# output_charlieplex_12x11.net
KiCad netlist of a schematic drawn in EasyEDA
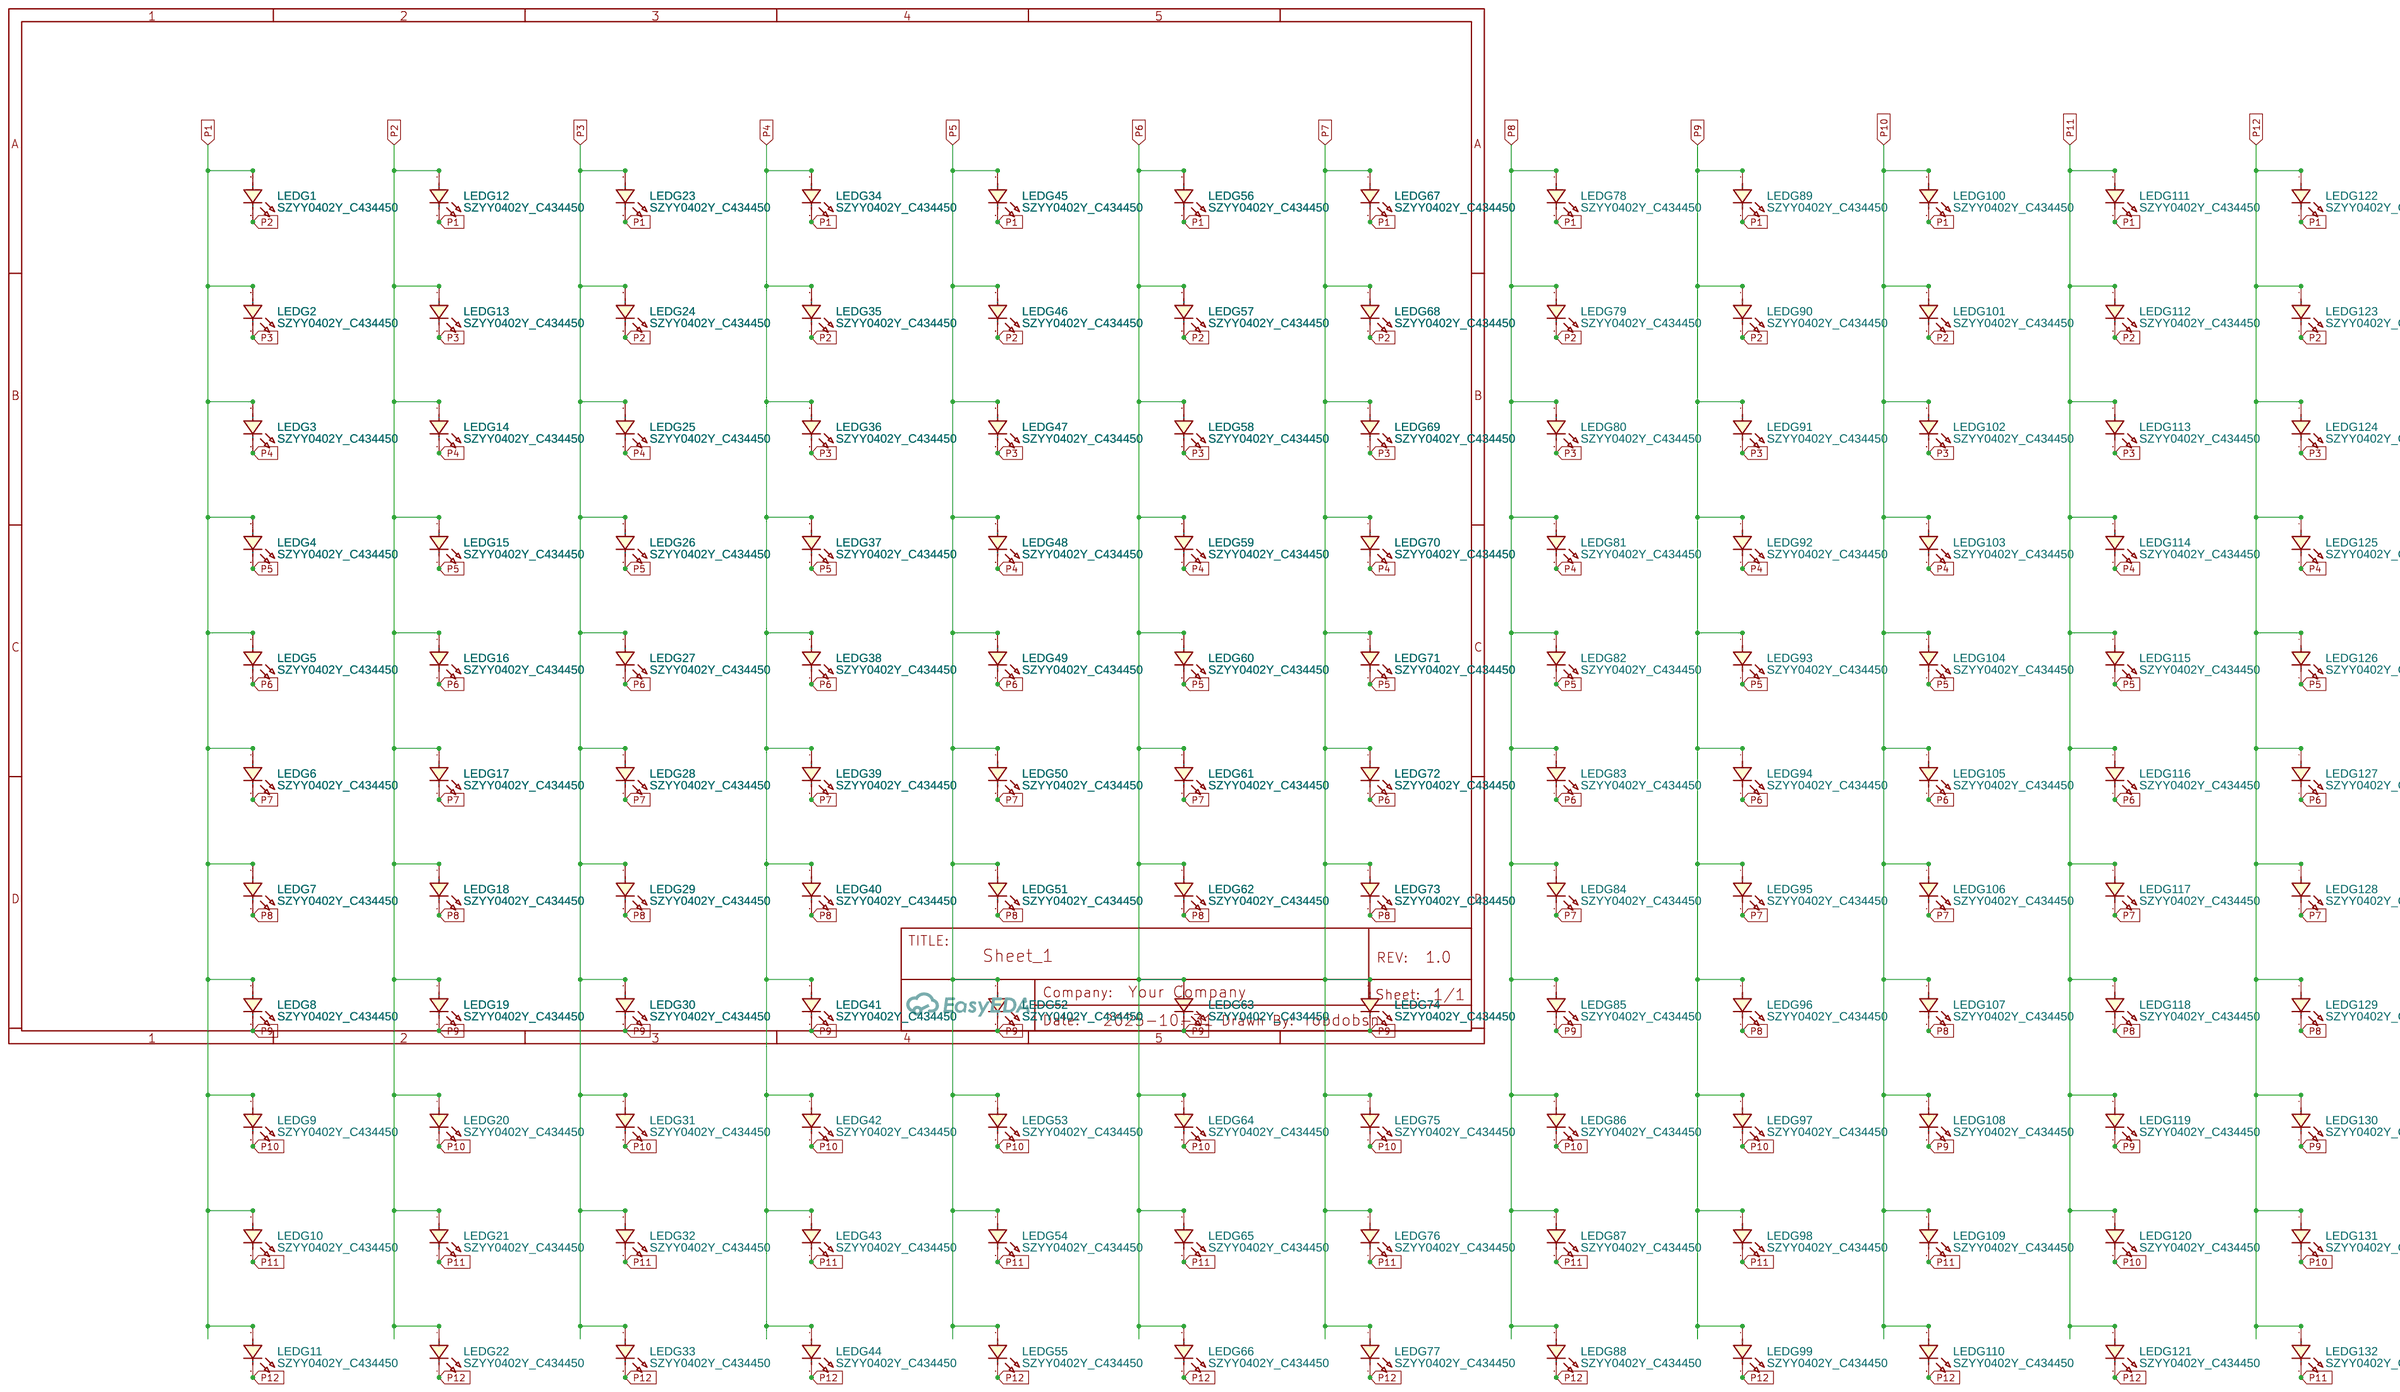
[diagram p0: schematic sheet]

(export (version "E")
  (design (tool "Eeschema 10.0.6"))
  (components
    (comp (ref "LEDG1")
      (value "SZYY0402Y_C434450")
      (fields (field (name "Manufacturer Part") "SZYY0402Y") (field (name "Manufacturer") "yongyu(永裕光电)"))
      (libsource (lib "") (part "SZYY0402Y_C434450"))
    )
    (comp (ref "LEDG2")
      (value "SZYY0402Y_C434450")
      (fields (field (name "Manufacturer Part") "SZYY0402Y") (field (name "Manufacturer") "yongyu(永裕光电)"))
      (libsource (lib "") (part "SZYY0402Y_C434450"))
    )
    (comp (ref "LEDG3")
      (value "SZYY0402Y_C434450")
      (fields (field (name "Manufacturer Part") "SZYY0402Y") (field (name "Manufacturer") "yongyu(永裕光电)"))
      (libsource (lib "") (part "SZYY0402Y_C434450"))
    )
    (comp (ref "LEDG4")
      (value "SZYY0402Y_C434450")
      (fields (field (name "Manufacturer Part") "SZYY0402Y") (field (name "Manufacturer") "yongyu(永裕光电)"))
      (libsource (lib "") (part "SZYY0402Y_C434450"))
    )
    (comp (ref "LEDG5")
      (value "SZYY0402Y_C434450")
      (fields (field (name "Manufacturer Part") "SZYY0402Y") (field (name "Manufacturer") "yongyu(永裕光电)"))
      (libsource (lib "") (part "SZYY0402Y_C434450"))
    )
    (comp (ref "LEDG6")
      (value "SZYY0402Y_C434450")
      (fields (field (name "Manufacturer Part") "SZYY0402Y") (field (name "Manufacturer") "yongyu(永裕光电)"))
      (libsource (lib "") (part "SZYY0402Y_C434450"))
    )
    (comp (ref "LEDG7")
      (value "SZYY0402Y_C434450")
      (fields (field (name "Manufacturer Part") "SZYY0402Y") (field (name "Manufacturer") "yongyu(永裕光电)"))
      (libsource (lib "") (part "SZYY0402Y_C434450"))
    )
    (comp (ref "LEDG8")
      (value "SZYY0402Y_C434450")
      (fields (field (name "Manufacturer Part") "SZYY0402Y") (field (name "Manufacturer") "yongyu(永裕光电)"))
      (libsource (lib "") (part "SZYY0402Y_C434450"))
    )
    (comp (ref "LEDG9")
      (value "SZYY0402Y_C434450")
      (fields (field (name "Manufacturer Part") "SZYY0402Y") (field (name "Manufacturer") "yongyu(永裕光电)"))
      (libsource (lib "") (part "SZYY0402Y_C434450"))
    )
    (comp (ref "LEDG10")
      (value "SZYY0402Y_C434450")
      (fields (field (name "Manufacturer Part") "SZYY0402Y") (field (name "Manufacturer") "yongyu(永裕光电)"))
      (libsource (lib "") (part "SZYY0402Y_C434450"))
    )
    (comp (ref "LEDG11")
      (value "SZYY0402Y_C434450")
      (fields (field (name "Manufacturer Part") "SZYY0402Y") (field (name "Manufacturer") "yongyu(永裕光电)"))
      (libsource (lib "") (part "SZYY0402Y_C434450"))
    )
    (comp (ref "LEDG12")
      (value "SZYY0402Y_C434450")
      (fields (field (name "Manufacturer Part") "SZYY0402Y") (field (name "Manufacturer") "yongyu(永裕光电)"))
      (libsource (lib "") (part "SZYY0402Y_C434450"))
    )
    (comp (ref "LEDG13")
      (value "SZYY0402Y_C434450")
      (fields (field (name "Manufacturer Part") "SZYY0402Y") (field (name "Manufacturer") "yongyu(永裕光电)"))
      (libsource (lib "") (part "SZYY0402Y_C434450"))
    )
    (comp (ref "LEDG14")
      (value "SZYY0402Y_C434450")
      (fields (field (name "Manufacturer Part") "SZYY0402Y") (field (name "Manufacturer") "yongyu(永裕光电)"))
      (libsource (lib "") (part "SZYY0402Y_C434450"))
    )
    (comp (ref "LEDG15")
      (value "SZYY0402Y_C434450")
      (fields (field (name "Manufacturer Part") "SZYY0402Y") (field (name "Manufacturer") "yongyu(永裕光电)"))
      (libsource (lib "") (part "SZYY0402Y_C434450"))
    )
    (comp (ref "LEDG16")
      (value "SZYY0402Y_C434450")
      (fields (field (name "Manufacturer Part") "SZYY0402Y") (field (name "Manufacturer") "yongyu(永裕光电)"))
      (libsource (lib "") (part "SZYY0402Y_C434450"))
    )
    (comp (ref "LEDG17")
      (value "SZYY0402Y_C434450")
      (fields (field (name "Manufacturer Part") "SZYY0402Y") (field (name "Manufacturer") "yongyu(永裕光电)"))
      (libsource (lib "") (part "SZYY0402Y_C434450"))
    )
    (comp (ref "LEDG18")
      (value "SZYY0402Y_C434450")
      (fields (field (name "Manufacturer Part") "SZYY0402Y") (field (name "Manufacturer") "yongyu(永裕光电)"))
      (libsource (lib "") (part "SZYY0402Y_C434450"))
    )
    (comp (ref "LEDG19")
      (value "SZYY0402Y_C434450")
      (fields (field (name "Manufacturer Part") "SZYY0402Y") (field (name "Manufacturer") "yongyu(永裕光电)"))
      (libsource (lib "") (part "SZYY0402Y_C434450"))
    )
    (comp (ref "LEDG20")
      (value "SZYY0402Y_C434450")
      (fields (field (name "Manufacturer Part") "SZYY0402Y") (field (name "Manufacturer") "yongyu(永裕光电)"))
      (libsource (lib "") (part "SZYY0402Y_C434450"))
    )
    (comp (ref "LEDG21")
      (value "SZYY0402Y_C434450")
      (fields (field (name "Manufacturer Part") "SZYY0402Y") (field (name "Manufacturer") "yongyu(永裕光电)"))
      (libsource (lib "") (part "SZYY0402Y_C434450"))
    )
    (comp (ref "LEDG22")
      (value "SZYY0402Y_C434450")
      (fields (field (name "Manufacturer Part") "SZYY0402Y") (field (name "Manufacturer") "yongyu(永裕光电)"))
      (libsource (lib "") (part "SZYY0402Y_C434450"))
    )
    (comp (ref "LEDG23")
      (value "SZYY0402Y_C434450")
      (fields (field (name "Manufacturer Part") "SZYY0402Y") (field (name "Manufacturer") "yongyu(永裕光电)"))
      (libsource (lib "") (part "SZYY0402Y_C434450"))
    )
    (comp (ref "LEDG24")
      (value "SZYY0402Y_C434450")
      (fields (field (name "Manufacturer Part") "SZYY0402Y") (field (name "Manufacturer") "yongyu(永裕光电)"))
      (libsource (lib "") (part "SZYY0402Y_C434450"))
    )
    (comp (ref "LEDG25")
      (value "SZYY0402Y_C434450")
      (fields (field (name "Manufacturer Part") "SZYY0402Y") (field (name "Manufacturer") "yongyu(永裕光电)"))
      (libsource (lib "") (part "SZYY0402Y_C434450"))
    )
    (comp (ref "LEDG26")
      (value "SZYY0402Y_C434450")
      (fields (field (name "Manufacturer Part") "SZYY0402Y") (field (name "Manufacturer") "yongyu(永裕光电)"))
      (libsource (lib "") (part "SZYY0402Y_C434450"))
    )
    (comp (ref "LEDG27")
      (value "SZYY0402Y_C434450")
      (fields (field (name "Manufacturer Part") "SZYY0402Y") (field (name "Manufacturer") "yongyu(永裕光电)"))
      (libsource (lib "") (part "SZYY0402Y_C434450"))
    )
    (comp (ref "LEDG28")
      (value "SZYY0402Y_C434450")
      (fields (field (name "Manufacturer Part") "SZYY0402Y") (field (name "Manufacturer") "yongyu(永裕光电)"))
      (libsource (lib "") (part "SZYY0402Y_C434450"))
    )
    (comp (ref "LEDG29")
      (value "SZYY0402Y_C434450")
      (fields (field (name "Manufacturer Part") "SZYY0402Y") (field (name "Manufacturer") "yongyu(永裕光电)"))
      (libsource (lib "") (part "SZYY0402Y_C434450"))
    )
    (comp (ref "LEDG30")
      (value "SZYY0402Y_C434450")
      (fields (field (name "Manufacturer Part") "SZYY0402Y") (field (name "Manufacturer") "yongyu(永裕光电)"))
      (libsource (lib "") (part "SZYY0402Y_C434450"))
    )
    (comp (ref "LEDG31")
      (value "SZYY0402Y_C434450")
      (fields (field (name "Manufacturer Part") "SZYY0402Y") (field (name "Manufacturer") "yongyu(永裕光电)"))
      (libsource (lib "") (part "SZYY0402Y_C434450"))
    )
    (comp (ref "LEDG32")
      (value "SZYY0402Y_C434450")
      (fields (field (name "Manufacturer Part") "SZYY0402Y") (field (name "Manufacturer") "yongyu(永裕光电)"))
      (libsource (lib "") (part "SZYY0402Y_C434450"))
    )
    (comp (ref "LEDG33")
      (value "SZYY0402Y_C434450")
      (fields (field (name "Manufacturer Part") "SZYY0402Y") (field (name "Manufacturer") "yongyu(永裕光电)"))
      (libsource (lib "") (part "SZYY0402Y_C434450"))
    )
    (comp (ref "LEDG34")
      (value "SZYY0402Y_C434450")
      (fields (field (name "Manufacturer Part") "SZYY0402Y") (field (name "Manufacturer") "yongyu(永裕光电)"))
      (libsource (lib "") (part "SZYY0402Y_C434450"))
    )
    (comp (ref "LEDG35")
      (value "SZYY0402Y_C434450")
      (fields (field (name "Manufacturer Part") "SZYY0402Y") (field (name "Manufacturer") "yongyu(永裕光电)"))
      (libsource (lib "") (part "SZYY0402Y_C434450"))
    )
    (comp (ref "LEDG36")
      (value "SZYY0402Y_C434450")
      (fields (field (name "Manufacturer Part") "SZYY0402Y") (field (name "Manufacturer") "yongyu(永裕光电)"))
      (libsource (lib "") (part "SZYY0402Y_C434450"))
    )
    (comp (ref "LEDG37")
      (value "SZYY0402Y_C434450")
      (fields (field (name "Manufacturer Part") "SZYY0402Y") (field (name "Manufacturer") "yongyu(永裕光电)"))
      (libsource (lib "") (part "SZYY0402Y_C434450"))
    )
    (comp (ref "LEDG38")
      (value "SZYY0402Y_C434450")
      (fields (field (name "Manufacturer Part") "SZYY0402Y") (field (name "Manufacturer") "yongyu(永裕光电)"))
      (libsource (lib "") (part "SZYY0402Y_C434450"))
    )
    (comp (ref "LEDG39")
      (value "SZYY0402Y_C434450")
      (fields (field (name "Manufacturer Part") "SZYY0402Y") (field (name "Manufacturer") "yongyu(永裕光电)"))
      (libsource (lib "") (part "SZYY0402Y_C434450"))
    )
    (comp (ref "LEDG40")
      (value "SZYY0402Y_C434450")
      (fields (field (name "Manufacturer Part") "SZYY0402Y") (field (name "Manufacturer") "yongyu(永裕光电)"))
      (libsource (lib "") (part "SZYY0402Y_C434450"))
    )
    (comp (ref "LEDG41")
      (value "SZYY0402Y_C434450")
      (fields (field (name "Manufacturer Part") "SZYY0402Y") (field (name "Manufacturer") "yongyu(永裕光电)"))
      (libsource (lib "") (part "SZYY0402Y_C434450"))
    )
    (comp (ref "LEDG42")
      (value "SZYY0402Y_C434450")
      (fields (field (name "Manufacturer Part") "SZYY0402Y") (field (name "Manufacturer") "yongyu(永裕光电)"))
      (libsource (lib "") (part "SZYY0402Y_C434450"))
    )
    (comp (ref "LEDG43")
      (value "SZYY0402Y_C434450")
      (fields (field (name "Manufacturer Part") "SZYY0402Y") (field (name "Manufacturer") "yongyu(永裕光电)"))
      (libsource (lib "") (part "SZYY0402Y_C434450"))
    )
    (comp (ref "LEDG44")
      (value "SZYY0402Y_C434450")
      (fields (field (name "Manufacturer Part") "SZYY0402Y") (field (name "Manufacturer") "yongyu(永裕光电)"))
      (libsource (lib "") (part "SZYY0402Y_C434450"))
    )
    (comp (ref "LEDG45")
      (value "SZYY0402Y_C434450")
      (fields (field (name "Manufacturer Part") "SZYY0402Y") (field (name "Manufacturer") "yongyu(永裕光电)"))
      (libsource (lib "") (part "SZYY0402Y_C434450"))
    )
    (comp (ref "LEDG46")
      (value "SZYY0402Y_C434450")
      (fields (field (name "Manufacturer Part") "SZYY0402Y") (field (name "Manufacturer") "yongyu(永裕光电)"))
      (libsource (lib "") (part "SZYY0402Y_C434450"))
    )
    (comp (ref "LEDG47")
      (value "SZYY0402Y_C434450")
      (fields (field (name "Manufacturer Part") "SZYY0402Y") (field (name "Manufacturer") "yongyu(永裕光电)"))
      (libsource (lib "") (part "SZYY0402Y_C434450"))
    )
    (comp (ref "LEDG48")
      (value "SZYY0402Y_C434450")
      (fields (field (name "Manufacturer Part") "SZYY0402Y") (field (name "Manufacturer") "yongyu(永裕光电)"))
      (libsource (lib "") (part "SZYY0402Y_C434450"))
    )
    (comp (ref "LEDG49")
      (value "SZYY0402Y_C434450")
      (fields (field (name "Manufacturer Part") "SZYY0402Y") (field (name "Manufacturer") "yongyu(永裕光电)"))
      (libsource (lib "") (part "SZYY0402Y_C434450"))
    )
    (comp (ref "LEDG50")
      (value "SZYY0402Y_C434450")
      (fields (field (name "Manufacturer Part") "SZYY0402Y") (field (name "Manufacturer") "yongyu(永裕光电)"))
      (libsource (lib "") (part "SZYY0402Y_C434450"))
    )
    (comp (ref "LEDG51")
      (value "SZYY0402Y_C434450")
      (fields (field (name "Manufacturer Part") "SZYY0402Y") (field (name "Manufacturer") "yongyu(永裕光电)"))
      (libsource (lib "") (part "SZYY0402Y_C434450"))
    )
    (comp (ref "LEDG52")
      (value "SZYY0402Y_C434450")
      (fields (field (name "Manufacturer Part") "SZYY0402Y") (field (name "Manufacturer") "yongyu(永裕光电)"))
      (libsource (lib "") (part "SZYY0402Y_C434450"))
    )
    (comp (ref "LEDG53")
      (value "SZYY0402Y_C434450")
      (fields (field (name "Manufacturer Part") "SZYY0402Y") (field (name "Manufacturer") "yongyu(永裕光电)"))
      (libsource (lib "") (part "SZYY0402Y_C434450"))
    )
    (comp (ref "LEDG54")
      (value "SZYY0402Y_C434450")
      (fields (field (name "Manufacturer Part") "SZYY0402Y") (field (name "Manufacturer") "yongyu(永裕光电)"))
      (libsource (lib "") (part "SZYY0402Y_C434450"))
    )
    (comp (ref "LEDG55")
      (value "SZYY0402Y_C434450")
      (fields (field (name "Manufacturer Part") "SZYY0402Y") (field (name "Manufacturer") "yongyu(永裕光电)"))
      (libsource (lib "") (part "SZYY0402Y_C434450"))
    )
    (comp (ref "LEDG56")
      (value "SZYY0402Y_C434450")
      (fields (field (name "Manufacturer Part") "SZYY0402Y") (field (name "Manufacturer") "yongyu(永裕光电)"))
      (libsource (lib "") (part "SZYY0402Y_C434450"))
    )
    (comp (ref "LEDG57")
      (value "SZYY0402Y_C434450")
      (fields (field (name "Manufacturer Part") "SZYY0402Y") (field (name "Manufacturer") "yongyu(永裕光电)"))
      (libsource (lib "") (part "SZYY0402Y_C434450"))
    )
    (comp (ref "LEDG58")
      (value "SZYY0402Y_C434450")
      (fields (field (name "Manufacturer Part") "SZYY0402Y") (field (name "Manufacturer") "yongyu(永裕光电)"))
      (libsource (lib "") (part "SZYY0402Y_C434450"))
    )
    (comp (ref "LEDG59")
      (value "SZYY0402Y_C434450")
      (fields (field (name "Manufacturer Part") "SZYY0402Y") (field (name "Manufacturer") "yongyu(永裕光电)"))
      (libsource (lib "") (part "SZYY0402Y_C434450"))
    )
    (comp (ref "LEDG60")
      (value "SZYY0402Y_C434450")
      (fields (field (name "Manufacturer Part") "SZYY0402Y") (field (name "Manufacturer") "yongyu(永裕光电)"))
      (libsource (lib "") (part "SZYY0402Y_C434450"))
    )
    (comp (ref "LEDG61")
      (value "SZYY0402Y_C434450")
      (fields (field (name "Manufacturer Part") "SZYY0402Y") (field (name "Manufacturer") "yongyu(永裕光电)"))
      (libsource (lib "") (part "SZYY0402Y_C434450"))
    )
    (comp (ref "LEDG62")
      (value "SZYY0402Y_C434450")
      (fields (field (name "Manufacturer Part") "SZYY0402Y") (field (name "Manufacturer") "yongyu(永裕光电)"))
      (libsource (lib "") (part "SZYY0402Y_C434450"))
    )
    (comp (ref "LEDG63")
      (value "SZYY0402Y_C434450")
      (fields (field (name "Manufacturer Part") "SZYY0402Y") (field (name "Manufacturer") "yongyu(永裕光电)"))
      (libsource (lib "") (part "SZYY0402Y_C434450"))
    )
    (comp (ref "LEDG64")
      (value "SZYY0402Y_C434450")
      (fields (field (name "Manufacturer Part") "SZYY0402Y") (field (name "Manufacturer") "yongyu(永裕光电)"))
      (libsource (lib "") (part "SZYY0402Y_C434450"))
    )
    (comp (ref "LEDG65")
      (value "SZYY0402Y_C434450")
      (fields (field (name "Manufacturer Part") "SZYY0402Y") (field (name "Manufacturer") "yongyu(永裕光电)"))
      (libsource (lib "") (part "SZYY0402Y_C434450"))
    )
    (comp (ref "LEDG66")
      (value "SZYY0402Y_C434450")
      (fields (field (name "Manufacturer Part") "SZYY0402Y") (field (name "Manufacturer") "yongyu(永裕光电)"))
      (libsource (lib "") (part "SZYY0402Y_C434450"))
    )
    (comp (ref "LEDG67")
      (value "SZYY0402Y_C434450")
      (fields (field (name "Manufacturer Part") "SZYY0402Y") (field (name "Manufacturer") "yongyu(永裕光电)"))
      (libsource (lib "") (part "SZYY0402Y_C434450"))
    )
    (comp (ref "LEDG68")
      (value "SZYY0402Y_C434450")
      (fields (field (name "Manufacturer Part") "SZYY0402Y") (field (name "Manufacturer") "yongyu(永裕光电)"))
      (libsource (lib "") (part "SZYY0402Y_C434450"))
    )
    (comp (ref "LEDG69")
      (value "SZYY0402Y_C434450")
      (fields (field (name "Manufacturer Part") "SZYY0402Y") (field (name "Manufacturer") "yongyu(永裕光电)"))
      (libsource (lib "") (part "SZYY0402Y_C434450"))
    )
    (comp (ref "LEDG70")
      (value "SZYY0402Y_C434450")
      (fields (field (name "Manufacturer Part") "SZYY0402Y") (field (name "Manufacturer") "yongyu(永裕光电)"))
      (libsource (lib "") (part "SZYY0402Y_C434450"))
    )
    (comp (ref "LEDG71")
      (value "SZYY0402Y_C434450")
      (fields (field (name "Manufacturer Part") "SZYY0402Y") (field (name "Manufacturer") "yongyu(永裕光电)"))
      (libsource (lib "") (part "SZYY0402Y_C434450"))
    )
    (comp (ref "LEDG72")
      (value "SZYY0402Y_C434450")
      (fields (field (name "Manufacturer Part") "SZYY0402Y") (field (name "Manufacturer") "yongyu(永裕光电)"))
      (libsource (lib "") (part "SZYY0402Y_C434450"))
    )
    (comp (ref "LEDG73")
      (value "SZYY0402Y_C434450")
      (fields (field (name "Manufacturer Part") "SZYY0402Y") (field (name "Manufacturer") "yongyu(永裕光电)"))
      (libsource (lib "") (part "SZYY0402Y_C434450"))
    )
    (comp (ref "LEDG74")
      (value "SZYY0402Y_C434450")
      (fields (field (name "Manufacturer Part") "SZYY0402Y") (field (name "Manufacturer") "yongyu(永裕光电)"))
      (libsource (lib "") (part "SZYY0402Y_C434450"))
    )
    (comp (ref "LEDG75")
      (value "SZYY0402Y_C434450")
      (fields (field (name "Manufacturer Part") "SZYY0402Y") (field (name "Manufacturer") "yongyu(永裕光电)"))
      (libsource (lib "") (part "SZYY0402Y_C434450"))
    )
    (comp (ref "LEDG76")
      (value "SZYY0402Y_C434450")
      (fields (field (name "Manufacturer Part") "SZYY0402Y") (field (name "Manufacturer") "yongyu(永裕光电)"))
      (libsource (lib "") (part "SZYY0402Y_C434450"))
    )
    (comp (ref "LEDG77")
      (value "SZYY0402Y_C434450")
      (fields (field (name "Manufacturer Part") "SZYY0402Y") (field (name "Manufacturer") "yongyu(永裕光电)"))
      (libsource (lib "") (part "SZYY0402Y_C434450"))
    )
    (comp (ref "LEDG78")
      (value "SZYY0402Y_C434450")
      (fields (field (name "Manufacturer Part") "SZYY0402Y") (field (name "Manufacturer") "yongyu(永裕光电)"))
      (libsource (lib "") (part "SZYY0402Y_C434450"))
    )
    (comp (ref "LEDG79")
      (value "SZYY0402Y_C434450")
      (fields (field (name "Manufacturer Part") "SZYY0402Y") (field (name "Manufacturer") "yongyu(永裕光电)"))
      (libsource (lib "") (part "SZYY0402Y_C434450"))
    )
    (comp (ref "LEDG80")
      (value "SZYY0402Y_C434450")
      (fields (field (name "Manufacturer Part") "SZYY0402Y") (field (name "Manufacturer") "yongyu(永裕光电)"))
      (libsource (lib "") (part "SZYY0402Y_C434450"))
    )
    (comp (ref "LEDG81")
      (value "SZYY0402Y_C434450")
      (fields (field (name "Manufacturer Part") "SZYY0402Y") (field (name "Manufacturer") "yongyu(永裕光电)"))
      (libsource (lib "") (part "SZYY0402Y_C434450"))
    )
    (comp (ref "LEDG82")
      (value "SZYY0402Y_C434450")
      (fields (field (name "Manufacturer Part") "SZYY0402Y") (field (name "Manufacturer") "yongyu(永裕光电)"))
      (libsource (lib "") (part "SZYY0402Y_C434450"))
    )
    (comp (ref "LEDG83")
      (value "SZYY0402Y_C434450")
      (fields (field (name "Manufacturer Part") "SZYY0402Y") (field (name "Manufacturer") "yongyu(永裕光电)"))
      (libsource (lib "") (part "SZYY0402Y_C434450"))
    )
    (comp (ref "LEDG84")
      (value "SZYY0402Y_C434450")
      (fields (field (name "Manufacturer Part") "SZYY0402Y") (field (name "Manufacturer") "yongyu(永裕光电)"))
      (libsource (lib "") (part "SZYY0402Y_C434450"))
    )
    (comp (ref "LEDG85")
      (value "SZYY0402Y_C434450")
      (fields (field (name "Manufacturer Part") "SZYY0402Y") (field (name "Manufacturer") "yongyu(永裕光电)"))
      (libsource (lib "") (part "SZYY0402Y_C434450"))
    )
    (comp (ref "LEDG86")
      (value "SZYY0402Y_C434450")
      (fields (field (name "Manufacturer Part") "SZYY0402Y") (field (name "Manufacturer") "yongyu(永裕光电)"))
      (libsource (lib "") (part "SZYY0402Y_C434450"))
    )
    (comp (ref "LEDG87")
      (value "SZYY0402Y_C434450")
      (fields (field (name "Manufacturer Part") "SZYY0402Y") (field (name "Manufacturer") "yongyu(永裕光电)"))
      (libsource (lib "") (part "SZYY0402Y_C434450"))
    )
    (comp (ref "LEDG88")
      (value "SZYY0402Y_C434450")
      (fields (field (name "Manufacturer Part") "SZYY0402Y") (field (name "Manufacturer") "yongyu(永裕光电)"))
      (libsource (lib "") (part "SZYY0402Y_C434450"))
    )
    (comp (ref "LEDG89")
      (value "SZYY0402Y_C434450")
      (fields (field (name "Manufacturer Part") "SZYY0402Y") (field (name "Manufacturer") "yongyu(永裕光电)"))
      (libsource (lib "") (part "SZYY0402Y_C434450"))
    )
    (comp (ref "LEDG90")
      (value "SZYY0402Y_C434450")
      (fields (field (name "Manufacturer Part") "SZYY0402Y") (field (name "Manufacturer") "yongyu(永裕光电)"))
      (libsource (lib "") (part "SZYY0402Y_C434450"))
    )
    (comp (ref "LEDG91")
      (value "SZYY0402Y_C434450")
      (fields (field (name "Manufacturer Part") "SZYY0402Y") (field (name "Manufacturer") "yongyu(永裕光电)"))
      (libsource (lib "") (part "SZYY0402Y_C434450"))
    )
    (comp (ref "LEDG92")
      (value "SZYY0402Y_C434450")
      (fields (field (name "Manufacturer Part") "SZYY0402Y") (field (name "Manufacturer") "yongyu(永裕光电)"))
      (libsource (lib "") (part "SZYY0402Y_C434450"))
    )
    (comp (ref "LEDG93")
      (value "SZYY0402Y_C434450")
      (fields (field (name "Manufacturer Part") "SZYY0402Y") (field (name "Manufacturer") "yongyu(永裕光电)"))
      (libsource (lib "") (part "SZYY0402Y_C434450"))
    )
    (comp (ref "LEDG94")
      (value "SZYY0402Y_C434450")
      (fields (field (name "Manufacturer Part") "SZYY0402Y") (field (name "Manufacturer") "yongyu(永裕光电)"))
      (libsource (lib "") (part "SZYY0402Y_C434450"))
    )
    (comp (ref "LEDG95")
      (value "SZYY0402Y_C434450")
      (fields (field (name "Manufacturer Part") "SZYY0402Y") (field (name "Manufacturer") "yongyu(永裕光电)"))
      (libsource (lib "") (part "SZYY0402Y_C434450"))
    )
    (comp (ref "LEDG96")
      (value "SZYY0402Y_C434450")
      (fields (field (name "Manufacturer Part") "SZYY0402Y") (field (name "Manufacturer") "yongyu(永裕光电)"))
      (libsource (lib "") (part "SZYY0402Y_C434450"))
    )
    (comp (ref "LEDG97")
      (value "SZYY0402Y_C434450")
      (fields (field (name "Manufacturer Part") "SZYY0402Y") (field (name "Manufacturer") "yongyu(永裕光电)"))
      (libsource (lib "") (part "SZYY0402Y_C434450"))
    )
    (comp (ref "LEDG98")
      (value "SZYY0402Y_C434450")
      (fields (field (name "Manufacturer Part") "SZYY0402Y") (field (name "Manufacturer") "yongyu(永裕光电)"))
      (libsource (lib "") (part "SZYY0402Y_C434450"))
    )
    (comp (ref "LEDG99")
      (value "SZYY0402Y_C434450")
      (fields (field (name "Manufacturer Part") "SZYY0402Y") (field (name "Manufacturer") "yongyu(永裕光电)"))
      (libsource (lib "") (part "SZYY0402Y_C434450"))
    )
    (comp (ref "LEDG100")
      (value "SZYY0402Y_C434450")
      (fields (field (name "Manufacturer Part") "SZYY0402Y") (field (name "Manufacturer") "yongyu(永裕光电)"))
      (libsource (lib "") (part "SZYY0402Y_C434450"))
    )
    (comp (ref "LEDG101")
      (value "SZYY0402Y_C434450")
      (fields (field (name "Manufacturer Part") "SZYY0402Y") (field (name "Manufacturer") "yongyu(永裕光电)"))
      (libsource (lib "") (part "SZYY0402Y_C434450"))
    )
    (comp (ref "LEDG102")
      (value "SZYY0402Y_C434450")
      (fields (field (name "Manufacturer Part") "SZYY0402Y") (field (name "Manufacturer") "yongyu(永裕光电)"))
      (libsource (lib "") (part "SZYY0402Y_C434450"))
    )
    (comp (ref "LEDG103")
      (value "SZYY0402Y_C434450")
      (fields (field (name "Manufacturer Part") "SZYY0402Y") (field (name "Manufacturer") "yongyu(永裕光电)"))
      (libsource (lib "") (part "SZYY0402Y_C434450"))
    )
    (comp (ref "LEDG104")
      (value "SZYY0402Y_C434450")
      (fields (field (name "Manufacturer Part") "SZYY0402Y") (field (name "Manufacturer") "yongyu(永裕光电)"))
      (libsource (lib "") (part "SZYY0402Y_C434450"))
    )
    (comp (ref "LEDG105")
      (value "SZYY0402Y_C434450")
      (fields (field (name "Manufacturer Part") "SZYY0402Y") (field (name "Manufacturer") "yongyu(永裕光电)"))
      (libsource (lib "") (part "SZYY0402Y_C434450"))
    )
    (comp (ref "LEDG106")
      (value "SZYY0402Y_C434450")
      (fields (field (name "Manufacturer Part") "SZYY0402Y") (field (name "Manufacturer") "yongyu(永裕光电)"))
      (libsource (lib "") (part "SZYY0402Y_C434450"))
    )
    (comp (ref "LEDG107")
      (value "SZYY0402Y_C434450")
      (fields (field (name "Manufacturer Part") "SZYY0402Y") (field (name "Manufacturer") "yongyu(永裕光电)"))
      (libsource (lib "") (part "SZYY0402Y_C434450"))
    )
    (comp (ref "LEDG108")
      (value "SZYY0402Y_C434450")
      (fields (field (name "Manufacturer Part") "SZYY0402Y") (field (name "Manufacturer") "yongyu(永裕光电)"))
      (libsource (lib "") (part "SZYY0402Y_C434450"))
    )
    (comp (ref "LEDG109")
      (value "SZYY0402Y_C434450")
      (fields (field (name "Manufacturer Part") "SZYY0402Y") (field (name "Manufacturer") "yongyu(永裕光电)"))
      (libsource (lib "") (part "SZYY0402Y_C434450"))
    )
    (comp (ref "LEDG110")
      (value "SZYY0402Y_C434450")
      (fields (field (name "Manufacturer Part") "SZYY0402Y") (field (name "Manufacturer") "yongyu(永裕光电)"))
      (libsource (lib "") (part "SZYY0402Y_C434450"))
    )
    (comp (ref "LEDG111")
      (value "SZYY0402Y_C434450")
      (fields (field (name "Manufacturer Part") "SZYY0402Y") (field (name "Manufacturer") "yongyu(永裕光电)"))
      (libsource (lib "") (part "SZYY0402Y_C434450"))
    )
    (comp (ref "LEDG112")
      (value "SZYY0402Y_C434450")
      (fields (field (name "Manufacturer Part") "SZYY0402Y") (field (name "Manufacturer") "yongyu(永裕光电)"))
      (libsource (lib "") (part "SZYY0402Y_C434450"))
    )
    (comp (ref "LEDG113")
      (value "SZYY0402Y_C434450")
      (fields (field (name "Manufacturer Part") "SZYY0402Y") (field (name "Manufacturer") "yongyu(永裕光电)"))
      (libsource (lib "") (part "SZYY0402Y_C434450"))
    )
    (comp (ref "LEDG114")
      (value "SZYY0402Y_C434450")
      (fields (field (name "Manufacturer Part") "SZYY0402Y") (field (name "Manufacturer") "yongyu(永裕光电)"))
      (libsource (lib "") (part "SZYY0402Y_C434450"))
    )
    (comp (ref "LEDG115")
      (value "SZYY0402Y_C434450")
      (fields (field (name "Manufacturer Part") "SZYY0402Y") (field (name "Manufacturer") "yongyu(永裕光电)"))
      (libsource (lib "") (part "SZYY0402Y_C434450"))
    )
    (comp (ref "LEDG116")
      (value "SZYY0402Y_C434450")
      (fields (field (name "Manufacturer Part") "SZYY0402Y") (field (name "Manufacturer") "yongyu(永裕光电)"))
      (libsource (lib "") (part "SZYY0402Y_C434450"))
    )
    (comp (ref "LEDG117")
      (value "SZYY0402Y_C434450")
      (fields (field (name "Manufacturer Part") "SZYY0402Y") (field (name "Manufacturer") "yongyu(永裕光电)"))
      (libsource (lib "") (part "SZYY0402Y_C434450"))
    )
    (comp (ref "LEDG118")
      (value "SZYY0402Y_C434450")
      (fields (field (name "Manufacturer Part") "SZYY0402Y") (field (name "Manufacturer") "yongyu(永裕光电)"))
      (libsource (lib "") (part "SZYY0402Y_C434450"))
    )
    (comp (ref "LEDG119")
      (value "SZYY0402Y_C434450")
      (fields (field (name "Manufacturer Part") "SZYY0402Y") (field (name "Manufacturer") "yongyu(永裕光电)"))
      (libsource (lib "") (part "SZYY0402Y_C434450"))
    )
    (comp (ref "LEDG120")
      (value "SZYY0402Y_C434450")
      (fields (field (name "Manufacturer Part") "SZYY0402Y") (field (name "Manufacturer") "yongyu(永裕光电)"))
      (libsource (lib "") (part "SZYY0402Y_C434450"))
    )
    (comp (ref "LEDG121")
      (value "SZYY0402Y_C434450")
      (fields (field (name "Manufacturer Part") "SZYY0402Y") (field (name "Manufacturer") "yongyu(永裕光电)"))
      (libsource (lib "") (part "SZYY0402Y_C434450"))
    )
    (comp (ref "LEDG122")
      (value "SZYY0402Y_C434450")
      (fields (field (name "Manufacturer Part") "SZYY0402Y") (field (name "Manufacturer") "yongyu(永裕光电)"))
      (libsource (lib "") (part "SZYY0402Y_C434450"))
    )
    (comp (ref "LEDG123")
      (value "SZYY0402Y_C434450")
      (fields (field (name "Manufacturer Part") "SZYY0402Y") (field (name "Manufacturer") "yongyu(永裕光电)"))
      (libsource (lib "") (part "SZYY0402Y_C434450"))
    )
    (comp (ref "LEDG124")
      (value "SZYY0402Y_C434450")
      (fields (field (name "Manufacturer Part") "SZYY0402Y") (field (name "Manufacturer") "yongyu(永裕光电)"))
      (libsource (lib "") (part "SZYY0402Y_C434450"))
    )
    (comp (ref "LEDG125")
      (value "SZYY0402Y_C434450")
      (fields (field (name "Manufacturer Part") "SZYY0402Y") (field (name "Manufacturer") "yongyu(永裕光电)"))
      (libsource (lib "") (part "SZYY0402Y_C434450"))
    )
    (comp (ref "LEDG126")
      (value "SZYY0402Y_C434450")
      (fields (field (name "Manufacturer Part") "SZYY0402Y") (field (name "Manufacturer") "yongyu(永裕光电)"))
      (libsource (lib "") (part "SZYY0402Y_C434450"))
    )
    (comp (ref "LEDG127")
      (value "SZYY0402Y_C434450")
      (fields (field (name "Manufacturer Part") "SZYY0402Y") (field (name "Manufacturer") "yongyu(永裕光电)"))
      (libsource (lib "") (part "SZYY0402Y_C434450"))
    )
    (comp (ref "LEDG128")
      (value "SZYY0402Y_C434450")
      (fields (field (name "Manufacturer Part") "SZYY0402Y") (field (name "Manufacturer") "yongyu(永裕光电)"))
      (libsource (lib "") (part "SZYY0402Y_C434450"))
    )
    (comp (ref "LEDG129")
      (value "SZYY0402Y_C434450")
      (fields (field (name "Manufacturer Part") "SZYY0402Y") (field (name "Manufacturer") "yongyu(永裕光电)"))
      (libsource (lib "") (part "SZYY0402Y_C434450"))
    )
    (comp (ref "LEDG130")
      (value "SZYY0402Y_C434450")
      (fields (field (name "Manufacturer Part") "SZYY0402Y") (field (name "Manufacturer") "yongyu(永裕光电)"))
      (libsource (lib "") (part "SZYY0402Y_C434450"))
    )
    (comp (ref "LEDG131")
      (value "SZYY0402Y_C434450")
      (fields (field (name "Manufacturer Part") "SZYY0402Y") (field (name "Manufacturer") "yongyu(永裕光电)"))
      (libsource (lib "") (part "SZYY0402Y_C434450"))
    )
    (comp (ref "LEDG132")
      (value "SZYY0402Y_C434450")
      (fields (field (name "Manufacturer Part") "SZYY0402Y") (field (name "Manufacturer") "yongyu(永裕光电)"))
      (libsource (lib "") (part "SZYY0402Y_C434450"))
    )
  )
  (nets
    (net (code "1") (name "P1") (class "Default")
      (node (ref "LEDG1") (pin "1") (pinfunction "A_1") (pintype "unspecified"))
      (node (ref "LEDG10") (pin "1") (pinfunction "A_1") (pintype "unspecified"))
      (node (ref "LEDG100") (pin "2") (pinfunction "K_2") (pintype "unspecified"))
      (node (ref "LEDG11") (pin "1") (pinfunction "A_1") (pintype "unspecified"))
      (node (ref "LEDG111") (pin "2") (pinfunction "K_2") (pintype "unspecified"))
      (node (ref "LEDG12") (pin "2") (pinfunction "K_2") (pintype "unspecified"))
      (node (ref "LEDG122") (pin "2") (pinfunction "K_2") (pintype "unspecified"))
      (node (ref "LEDG2") (pin "1") (pinfunction "A_1") (pintype "unspecified"))
      (node (ref "LEDG23") (pin "2") (pinfunction "K_2") (pintype "unspecified"))
      (node (ref "LEDG3") (pin "1") (pinfunction "A_1") (pintype "unspecified"))
      (node (ref "LEDG34") (pin "2") (pinfunction "K_2") (pintype "unspecified"))
      (node (ref "LEDG4") (pin "1") (pinfunction "A_1") (pintype "unspecified"))
      (node (ref "LEDG45") (pin "2") (pinfunction "K_2") (pintype "unspecified"))
      (node (ref "LEDG5") (pin "1") (pinfunction "A_1") (pintype "unspecified"))
      (node (ref "LEDG56") (pin "2") (pinfunction "K_2") (pintype "unspecified"))
      (node (ref "LEDG6") (pin "1") (pinfunction "A_1") (pintype "unspecified"))
      (node (ref "LEDG67") (pin "2") (pinfunction "K_2") (pintype "unspecified"))
      (node (ref "LEDG7") (pin "1") (pinfunction "A_1") (pintype "unspecified"))
      (node (ref "LEDG78") (pin "2") (pinfunction "K_2") (pintype "unspecified"))
      (node (ref "LEDG8") (pin "1") (pinfunction "A_1") (pintype "unspecified"))
      (node (ref "LEDG89") (pin "2") (pinfunction "K_2") (pintype "unspecified"))
      (node (ref "LEDG9") (pin "1") (pinfunction "A_1") (pintype "unspecified"))
    )
    (net (code "2") (name "P2") (class "Default")
      (node (ref "LEDG1") (pin "2") (pinfunction "K_2") (pintype "unspecified"))
      (node (ref "LEDG101") (pin "2") (pinfunction "K_2") (pintype "unspecified"))
      (node (ref "LEDG112") (pin "2") (pinfunction "K_2") (pintype "unspecified"))
      (node (ref "LEDG12") (pin "1") (pinfunction "A_1") (pintype "unspecified"))
      (node (ref "LEDG123") (pin "2") (pinfunction "K_2") (pintype "unspecified"))
      (node (ref "LEDG13") (pin "1") (pinfunction "A_1") (pintype "unspecified"))
      (node (ref "LEDG14") (pin "1") (pinfunction "A_1") (pintype "unspecified"))
      (node (ref "LEDG15") (pin "1") (pinfunction "A_1") (pintype "unspecified"))
      (node (ref "LEDG16") (pin "1") (pinfunction "A_1") (pintype "unspecified"))
      (node (ref "LEDG17") (pin "1") (pinfunction "A_1") (pintype "unspecified"))
      (node (ref "LEDG18") (pin "1") (pinfunction "A_1") (pintype "unspecified"))
      (node (ref "LEDG19") (pin "1") (pinfunction "A_1") (pintype "unspecified"))
      (node (ref "LEDG20") (pin "1") (pinfunction "A_1") (pintype "unspecified"))
      (node (ref "LEDG21") (pin "1") (pinfunction "A_1") (pintype "unspecified"))
      (node (ref "LEDG22") (pin "1") (pinfunction "A_1") (pintype "unspecified"))
      (node (ref "LEDG24") (pin "2") (pinfunction "K_2") (pintype "unspecified"))
      (node (ref "LEDG35") (pin "2") (pinfunction "K_2") (pintype "unspecified"))
      (node (ref "LEDG46") (pin "2") (pinfunction "K_2") (pintype "unspecified"))
      (node (ref "LEDG57") (pin "2") (pinfunction "K_2") (pintype "unspecified"))
      (node (ref "LEDG68") (pin "2") (pinfunction "K_2") (pintype "unspecified"))
      (node (ref "LEDG79") (pin "2") (pinfunction "K_2") (pintype "unspecified"))
      (node (ref "LEDG90") (pin "2") (pinfunction "K_2") (pintype "unspecified"))
    )
    (net (code "3") (name "P3") (class "Default")
      (node (ref "LEDG102") (pin "2") (pinfunction "K_2") (pintype "unspecified"))
      (node (ref "LEDG113") (pin "2") (pinfunction "K_2") (pintype "unspecified"))
      (node (ref "LEDG124") (pin "2") (pinfunction "K_2") (pintype "unspecified"))
      (node (ref "LEDG13") (pin "2") (pinfunction "K_2") (pintype "unspecified"))
      (node (ref "LEDG2") (pin "2") (pinfunction "K_2") (pintype "unspecified"))
      (node (ref "LEDG23") (pin "1") (pinfunction "A_1") (pintype "unspecified"))
      (node (ref "LEDG24") (pin "1") (pinfunction "A_1") (pintype "unspecified"))
      (node (ref "LEDG25") (pin "1") (pinfunction "A_1") (pintype "unspecified"))
      (node (ref "LEDG26") (pin "1") (pinfunction "A_1") (pintype "unspecified"))
      (node (ref "LEDG27") (pin "1") (pinfunction "A_1") (pintype "unspecified"))
      (node (ref "LEDG28") (pin "1") (pinfunction "A_1") (pintype "unspecified"))
      (node (ref "LEDG29") (pin "1") (pinfunction "A_1") (pintype "unspecified"))
      (node (ref "LEDG30") (pin "1") (pinfunction "A_1") (pintype "unspecified"))
      (node (ref "LEDG31") (pin "1") (pinfunction "A_1") (pintype "unspecified"))
      (node (ref "LEDG32") (pin "1") (pinfunction "A_1") (pintype "unspecified"))
      (node (ref "LEDG33") (pin "1") (pinfunction "A_1") (pintype "unspecified"))
      (node (ref "LEDG36") (pin "2") (pinfunction "K_2") (pintype "unspecified"))
      (node (ref "LEDG47") (pin "2") (pinfunction "K_2") (pintype "unspecified"))
      (node (ref "LEDG58") (pin "2") (pinfunction "K_2") (pintype "unspecified"))
      (node (ref "LEDG69") (pin "2") (pinfunction "K_2") (pintype "unspecified"))
      (node (ref "LEDG80") (pin "2") (pinfunction "K_2") (pintype "unspecified"))
      (node (ref "LEDG91") (pin "2") (pinfunction "K_2") (pintype "unspecified"))
    )
    (net (code "4") (name "P4") (class "Default")
      (node (ref "LEDG103") (pin "2") (pinfunction "K_2") (pintype "unspecified"))
      (node (ref "LEDG114") (pin "2") (pinfunction "K_2") (pintype "unspecified"))
      (node (ref "LEDG125") (pin "2") (pinfunction "K_2") (pintype "unspecified"))
      (node (ref "LEDG14") (pin "2") (pinfunction "K_2") (pintype "unspecified"))
      (node (ref "LEDG25") (pin "2") (pinfunction "K_2") (pintype "unspecified"))
      (node (ref "LEDG3") (pin "2") (pinfunction "K_2") (pintype "unspecified"))
      (node (ref "LEDG34") (pin "1") (pinfunction "A_1") (pintype "unspecified"))
      (node (ref "LEDG35") (pin "1") (pinfunction "A_1") (pintype "unspecified"))
      (node (ref "LEDG36") (pin "1") (pinfunction "A_1") (pintype "unspecified"))
      (node (ref "LEDG37") (pin "1") (pinfunction "A_1") (pintype "unspecified"))
      (node (ref "LEDG38") (pin "1") (pinfunction "A_1") (pintype "unspecified"))
      (node (ref "LEDG39") (pin "1") (pinfunction "A_1") (pintype "unspecified"))
      (node (ref "LEDG40") (pin "1") (pinfunction "A_1") (pintype "unspecified"))
      (node (ref "LEDG41") (pin "1") (pinfunction "A_1") (pintype "unspecified"))
      (node (ref "LEDG42") (pin "1") (pinfunction "A_1") (pintype "unspecified"))
      (node (ref "LEDG43") (pin "1") (pinfunction "A_1") (pintype "unspecified"))
      (node (ref "LEDG44") (pin "1") (pinfunction "A_1") (pintype "unspecified"))
      (node (ref "LEDG48") (pin "2") (pinfunction "K_2") (pintype "unspecified"))
      (node (ref "LEDG59") (pin "2") (pinfunction "K_2") (pintype "unspecified"))
      (node (ref "LEDG70") (pin "2") (pinfunction "K_2") (pintype "unspecified"))
      (node (ref "LEDG81") (pin "2") (pinfunction "K_2") (pintype "unspecified"))
      (node (ref "LEDG92") (pin "2") (pinfunction "K_2") (pintype "unspecified"))
    )
    (net (code "5") (name "P5") (class "Default")
      (node (ref "LEDG104") (pin "2") (pinfunction "K_2") (pintype "unspecified"))
      (node (ref "LEDG115") (pin "2") (pinfunction "K_2") (pintype "unspecified"))
      (node (ref "LEDG126") (pin "2") (pinfunction "K_2") (pintype "unspecified"))
      (node (ref "LEDG15") (pin "2") (pinfunction "K_2") (pintype "unspecified"))
      (node (ref "LEDG26") (pin "2") (pinfunction "K_2") (pintype "unspecified"))
      (node (ref "LEDG37") (pin "2") (pinfunction "K_2") (pintype "unspecified"))
      (node (ref "LEDG4") (pin "2") (pinfunction "K_2") (pintype "unspecified"))
      (node (ref "LEDG45") (pin "1") (pinfunction "A_1") (pintype "unspecified"))
      (node (ref "LEDG46") (pin "1") (pinfunction "A_1") (pintype "unspecified"))
      (node (ref "LEDG47") (pin "1") (pinfunction "A_1") (pintype "unspecified"))
      (node (ref "LEDG48") (pin "1") (pinfunction "A_1") (pintype "unspecified"))
      (node (ref "LEDG49") (pin "1") (pinfunction "A_1") (pintype "unspecified"))
      (node (ref "LEDG50") (pin "1") (pinfunction "A_1") (pintype "unspecified"))
      (node (ref "LEDG51") (pin "1") (pinfunction "A_1") (pintype "unspecified"))
      (node (ref "LEDG52") (pin "1") (pinfunction "A_1") (pintype "unspecified"))
      (node (ref "LEDG53") (pin "1") (pinfunction "A_1") (pintype "unspecified"))
      (node (ref "LEDG54") (pin "1") (pinfunction "A_1") (pintype "unspecified"))
      (node (ref "LEDG55") (pin "1") (pinfunction "A_1") (pintype "unspecified"))
      (node (ref "LEDG60") (pin "2") (pinfunction "K_2") (pintype "unspecified"))
      (node (ref "LEDG71") (pin "2") (pinfunction "K_2") (pintype "unspecified"))
      (node (ref "LEDG82") (pin "2") (pinfunction "K_2") (pintype "unspecified"))
      (node (ref "LEDG93") (pin "2") (pinfunction "K_2") (pintype "unspecified"))
    )
    (net (code "6") (name "P6") (class "Default")
      (node (ref "LEDG105") (pin "2") (pinfunction "K_2") (pintype "unspecified"))
      (node (ref "LEDG116") (pin "2") (pinfunction "K_2") (pintype "unspecified"))
      (node (ref "LEDG127") (pin "2") (pinfunction "K_2") (pintype "unspecified"))
      (node (ref "LEDG16") (pin "2") (pinfunction "K_2") (pintype "unspecified"))
      (node (ref "LEDG27") (pin "2") (pinfunction "K_2") (pintype "unspecified"))
      (node (ref "LEDG38") (pin "2") (pinfunction "K_2") (pintype "unspecified"))
      (node (ref "LEDG49") (pin "2") (pinfunction "K_2") (pintype "unspecified"))
      (node (ref "LEDG5") (pin "2") (pinfunction "K_2") (pintype "unspecified"))
      (node (ref "LEDG56") (pin "1") (pinfunction "A_1") (pintype "unspecified"))
      (node (ref "LEDG57") (pin "1") (pinfunction "A_1") (pintype "unspecified"))
      (node (ref "LEDG58") (pin "1") (pinfunction "A_1") (pintype "unspecified"))
      (node (ref "LEDG59") (pin "1") (pinfunction "A_1") (pintype "unspecified"))
      (node (ref "LEDG60") (pin "1") (pinfunction "A_1") (pintype "unspecified"))
      (node (ref "LEDG61") (pin "1") (pinfunction "A_1") (pintype "unspecified"))
      (node (ref "LEDG62") (pin "1") (pinfunction "A_1") (pintype "unspecified"))
      (node (ref "LEDG63") (pin "1") (pinfunction "A_1") (pintype "unspecified"))
      (node (ref "LEDG64") (pin "1") (pinfunction "A_1") (pintype "unspecified"))
      (node (ref "LEDG65") (pin "1") (pinfunction "A_1") (pintype "unspecified"))
      (node (ref "LEDG66") (pin "1") (pinfunction "A_1") (pintype "unspecified"))
      (node (ref "LEDG72") (pin "2") (pinfunction "K_2") (pintype "unspecified"))
      (node (ref "LEDG83") (pin "2") (pinfunction "K_2") (pintype "unspecified"))
      (node (ref "LEDG94") (pin "2") (pinfunction "K_2") (pintype "unspecified"))
    )
    (net (code "7") (name "P7") (class "Default")
      (node (ref "LEDG106") (pin "2") (pinfunction "K_2") (pintype "unspecified"))
      (node (ref "LEDG117") (pin "2") (pinfunction "K_2") (pintype "unspecified"))
      (node (ref "LEDG128") (pin "2") (pinfunction "K_2") (pintype "unspecified"))
      (node (ref "LEDG17") (pin "2") (pinfunction "K_2") (pintype "unspecified"))
      (node (ref "LEDG28") (pin "2") (pinfunction "K_2") (pintype "unspecified"))
      (node (ref "LEDG39") (pin "2") (pinfunction "K_2") (pintype "unspecified"))
      (node (ref "LEDG50") (pin "2") (pinfunction "K_2") (pintype "unspecified"))
      (node (ref "LEDG6") (pin "2") (pinfunction "K_2") (pintype "unspecified"))
      (node (ref "LEDG61") (pin "2") (pinfunction "K_2") (pintype "unspecified"))
      (node (ref "LEDG67") (pin "1") (pinfunction "A_1") (pintype "unspecified"))
      (node (ref "LEDG68") (pin "1") (pinfunction "A_1") (pintype "unspecified"))
      (node (ref "LEDG69") (pin "1") (pinfunction "A_1") (pintype "unspecified"))
      (node (ref "LEDG70") (pin "1") (pinfunction "A_1") (pintype "unspecified"))
      (node (ref "LEDG71") (pin "1") (pinfunction "A_1") (pintype "unspecified"))
      (node (ref "LEDG72") (pin "1") (pinfunction "A_1") (pintype "unspecified"))
      (node (ref "LEDG73") (pin "1") (pinfunction "A_1") (pintype "unspecified"))
      (node (ref "LEDG74") (pin "1") (pinfunction "A_1") (pintype "unspecified"))
      (node (ref "LEDG75") (pin "1") (pinfunction "A_1") (pintype "unspecified"))
      (node (ref "LEDG76") (pin "1") (pinfunction "A_1") (pintype "unspecified"))
      (node (ref "LEDG77") (pin "1") (pinfunction "A_1") (pintype "unspecified"))
      (node (ref "LEDG84") (pin "2") (pinfunction "K_2") (pintype "unspecified"))
      (node (ref "LEDG95") (pin "2") (pinfunction "K_2") (pintype "unspecified"))
    )
    (net (code "8") (name "P8") (class "Default")
      (node (ref "LEDG107") (pin "2") (pinfunction "K_2") (pintype "unspecified"))
      (node (ref "LEDG118") (pin "2") (pinfunction "K_2") (pintype "unspecified"))
      (node (ref "LEDG129") (pin "2") (pinfunction "K_2") (pintype "unspecified"))
      (node (ref "LEDG18") (pin "2") (pinfunction "K_2") (pintype "unspecified"))
      (node (ref "LEDG29") (pin "2") (pinfunction "K_2") (pintype "unspecified"))
      (node (ref "LEDG40") (pin "2") (pinfunction "K_2") (pintype "unspecified"))
      (node (ref "LEDG51") (pin "2") (pinfunction "K_2") (pintype "unspecified"))
      (node (ref "LEDG62") (pin "2") (pinfunction "K_2") (pintype "unspecified"))
      (node (ref "LEDG7") (pin "2") (pinfunction "K_2") (pintype "unspecified"))
      (node (ref "LEDG73") (pin "2") (pinfunction "K_2") (pintype "unspecified"))
      (node (ref "LEDG78") (pin "1") (pinfunction "A_1") (pintype "unspecified"))
      (node (ref "LEDG79") (pin "1") (pinfunction "A_1") (pintype "unspecified"))
      (node (ref "LEDG80") (pin "1") (pinfunction "A_1") (pintype "unspecified"))
      (node (ref "LEDG81") (pin "1") (pinfunction "A_1") (pintype "unspecified"))
      (node (ref "LEDG82") (pin "1") (pinfunction "A_1") (pintype "unspecified"))
      (node (ref "LEDG83") (pin "1") (pinfunction "A_1") (pintype "unspecified"))
      (node (ref "LEDG84") (pin "1") (pinfunction "A_1") (pintype "unspecified"))
      (node (ref "LEDG85") (pin "1") (pinfunction "A_1") (pintype "unspecified"))
      (node (ref "LEDG86") (pin "1") (pinfunction "A_1") (pintype "unspecified"))
      (node (ref "LEDG87") (pin "1") (pinfunction "A_1") (pintype "unspecified"))
      (node (ref "LEDG88") (pin "1") (pinfunction "A_1") (pintype "unspecified"))
      (node (ref "LEDG96") (pin "2") (pinfunction "K_2") (pintype "unspecified"))
    )
    (net (code "9") (name "P9") (class "Default")
      (node (ref "LEDG108") (pin "2") (pinfunction "K_2") (pintype "unspecified"))
      (node (ref "LEDG119") (pin "2") (pinfunction "K_2") (pintype "unspecified"))
      (node (ref "LEDG130") (pin "2") (pinfunction "K_2") (pintype "unspecified"))
      (node (ref "LEDG19") (pin "2") (pinfunction "K_2") (pintype "unspecified"))
      (node (ref "LEDG30") (pin "2") (pinfunction "K_2") (pintype "unspecified"))
      (node (ref "LEDG41") (pin "2") (pinfunction "K_2") (pintype "unspecified"))
      (node (ref "LEDG52") (pin "2") (pinfunction "K_2") (pintype "unspecified"))
      (node (ref "LEDG63") (pin "2") (pinfunction "K_2") (pintype "unspecified"))
      (node (ref "LEDG74") (pin "2") (pinfunction "K_2") (pintype "unspecified"))
      (node (ref "LEDG8") (pin "2") (pinfunction "K_2") (pintype "unspecified"))
      (node (ref "LEDG85") (pin "2") (pinfunction "K_2") (pintype "unspecified"))
      (node (ref "LEDG89") (pin "1") (pinfunction "A_1") (pintype "unspecified"))
      (node (ref "LEDG90") (pin "1") (pinfunction "A_1") (pintype "unspecified"))
      (node (ref "LEDG91") (pin "1") (pinfunction "A_1") (pintype "unspecified"))
      (node (ref "LEDG92") (pin "1") (pinfunction "A_1") (pintype "unspecified"))
      (node (ref "LEDG93") (pin "1") (pinfunction "A_1") (pintype "unspecified"))
      (node (ref "LEDG94") (pin "1") (pinfunction "A_1") (pintype "unspecified"))
      (node (ref "LEDG95") (pin "1") (pinfunction "A_1") (pintype "unspecified"))
      (node (ref "LEDG96") (pin "1") (pinfunction "A_1") (pintype "unspecified"))
      (node (ref "LEDG97") (pin "1") (pinfunction "A_1") (pintype "unspecified"))
      (node (ref "LEDG98") (pin "1") (pinfunction "A_1") (pintype "unspecified"))
      (node (ref "LEDG99") (pin "1") (pinfunction "A_1") (pintype "unspecified"))
    )
    (net (code "10") (name "P10") (class "Default")
      (node (ref "LEDG100") (pin "1") (pinfunction "A_1") (pintype "unspecified"))
      (node (ref "LEDG101") (pin "1") (pinfunction "A_1") (pintype "unspecified"))
      (node (ref "LEDG102") (pin "1") (pinfunction "A_1") (pintype "unspecified"))
      (node (ref "LEDG103") (pin "1") (pinfunction "A_1") (pintype "unspecified"))
      (node (ref "LEDG104") (pin "1") (pinfunction "A_1") (pintype "unspecified"))
      (node (ref "LEDG105") (pin "1") (pinfunction "A_1") (pintype "unspecified"))
      (node (ref "LEDG106") (pin "1") (pinfunction "A_1") (pintype "unspecified"))
      (node (ref "LEDG107") (pin "1") (pinfunction "A_1") (pintype "unspecified"))
      (node (ref "LEDG108") (pin "1") (pinfunction "A_1") (pintype "unspecified"))
      (node (ref "LEDG109") (pin "1") (pinfunction "A_1") (pintype "unspecified"))
      (node (ref "LEDG110") (pin "1") (pinfunction "A_1") (pintype "unspecified"))
      (node (ref "LEDG120") (pin "2") (pinfunction "K_2") (pintype "unspecified"))
      (node (ref "LEDG131") (pin "2") (pinfunction "K_2") (pintype "unspecified"))
      (node (ref "LEDG20") (pin "2") (pinfunction "K_2") (pintype "unspecified"))
      (node (ref "LEDG31") (pin "2") (pinfunction "K_2") (pintype "unspecified"))
      (node (ref "LEDG42") (pin "2") (pinfunction "K_2") (pintype "unspecified"))
      (node (ref "LEDG53") (pin "2") (pinfunction "K_2") (pintype "unspecified"))
      (node (ref "LEDG64") (pin "2") (pinfunction "K_2") (pintype "unspecified"))
      (node (ref "LEDG75") (pin "2") (pinfunction "K_2") (pintype "unspecified"))
      (node (ref "LEDG86") (pin "2") (pinfunction "K_2") (pintype "unspecified"))
      (node (ref "LEDG9") (pin "2") (pinfunction "K_2") (pintype "unspecified"))
      (node (ref "LEDG97") (pin "2") (pinfunction "K_2") (pintype "unspecified"))
    )
    (net (code "11") (name "P11") (class "Default")
      (node (ref "LEDG10") (pin "2") (pinfunction "K_2") (pintype "unspecified"))
      (node (ref "LEDG109") (pin "2") (pinfunction "K_2") (pintype "unspecified"))
      (node (ref "LEDG111") (pin "1") (pinfunction "A_1") (pintype "unspecified"))
      (node (ref "LEDG112") (pin "1") (pinfunction "A_1") (pintype "unspecified"))
      (node (ref "LEDG113") (pin "1") (pinfunction "A_1") (pintype "unspecified"))
      (node (ref "LEDG114") (pin "1") (pinfunction "A_1") (pintype "unspecified"))
      (node (ref "LEDG115") (pin "1") (pinfunction "A_1") (pintype "unspecified"))
      (node (ref "LEDG116") (pin "1") (pinfunction "A_1") (pintype "unspecified"))
      (node (ref "LEDG117") (pin "1") (pinfunction "A_1") (pintype "unspecified"))
      (node (ref "LEDG118") (pin "1") (pinfunction "A_1") (pintype "unspecified"))
      (node (ref "LEDG119") (pin "1") (pinfunction "A_1") (pintype "unspecified"))
      (node (ref "LEDG120") (pin "1") (pinfunction "A_1") (pintype "unspecified"))
      (node (ref "LEDG121") (pin "1") (pinfunction "A_1") (pintype "unspecified"))
      (node (ref "LEDG132") (pin "2") (pinfunction "K_2") (pintype "unspecified"))
      (node (ref "LEDG21") (pin "2") (pinfunction "K_2") (pintype "unspecified"))
      (node (ref "LEDG32") (pin "2") (pinfunction "K_2") (pintype "unspecified"))
      (node (ref "LEDG43") (pin "2") (pinfunction "K_2") (pintype "unspecified"))
      (node (ref "LEDG54") (pin "2") (pinfunction "K_2") (pintype "unspecified"))
      (node (ref "LEDG65") (pin "2") (pinfunction "K_2") (pintype "unspecified"))
      (node (ref "LEDG76") (pin "2") (pinfunction "K_2") (pintype "unspecified"))
      (node (ref "LEDG87") (pin "2") (pinfunction "K_2") (pintype "unspecified"))
      (node (ref "LEDG98") (pin "2") (pinfunction "K_2") (pintype "unspecified"))
    )
    (net (code "12") (name "P12") (class "Default")
      (node (ref "LEDG11") (pin "2") (pinfunction "K_2") (pintype "unspecified"))
      (node (ref "LEDG110") (pin "2") (pinfunction "K_2") (pintype "unspecified"))
      (node (ref "LEDG121") (pin "2") (pinfunction "K_2") (pintype "unspecified"))
      (node (ref "LEDG122") (pin "1") (pinfunction "A_1") (pintype "unspecified"))
      (node (ref "LEDG123") (pin "1") (pinfunction "A_1") (pintype "unspecified"))
      (node (ref "LEDG124") (pin "1") (pinfunction "A_1") (pintype "unspecified"))
      (node (ref "LEDG125") (pin "1") (pinfunction "A_1") (pintype "unspecified"))
      (node (ref "LEDG126") (pin "1") (pinfunction "A_1") (pintype "unspecified"))
      (node (ref "LEDG127") (pin "1") (pinfunction "A_1") (pintype "unspecified"))
      (node (ref "LEDG128") (pin "1") (pinfunction "A_1") (pintype "unspecified"))
      (node (ref "LEDG129") (pin "1") (pinfunction "A_1") (pintype "unspecified"))
      (node (ref "LEDG130") (pin "1") (pinfunction "A_1") (pintype "unspecified"))
      (node (ref "LEDG131") (pin "1") (pinfunction "A_1") (pintype "unspecified"))
      (node (ref "LEDG132") (pin "1") (pinfunction "A_1") (pintype "unspecified"))
      (node (ref "LEDG22") (pin "2") (pinfunction "K_2") (pintype "unspecified"))
      (node (ref "LEDG33") (pin "2") (pinfunction "K_2") (pintype "unspecified"))
      (node (ref "LEDG44") (pin "2") (pinfunction "K_2") (pintype "unspecified"))
      (node (ref "LEDG55") (pin "2") (pinfunction "K_2") (pintype "unspecified"))
      (node (ref "LEDG66") (pin "2") (pinfunction "K_2") (pintype "unspecified"))
      (node (ref "LEDG77") (pin "2") (pinfunction "K_2") (pintype "unspecified"))
      (node (ref "LEDG88") (pin "2") (pinfunction "K_2") (pintype "unspecified"))
      (node (ref "LEDG99") (pin "2") (pinfunction "K_2") (pintype "unspecified"))
    )
  )
)
